# Power_Supply.net
KiCad netlist of a schematic drawn in Altium Designer
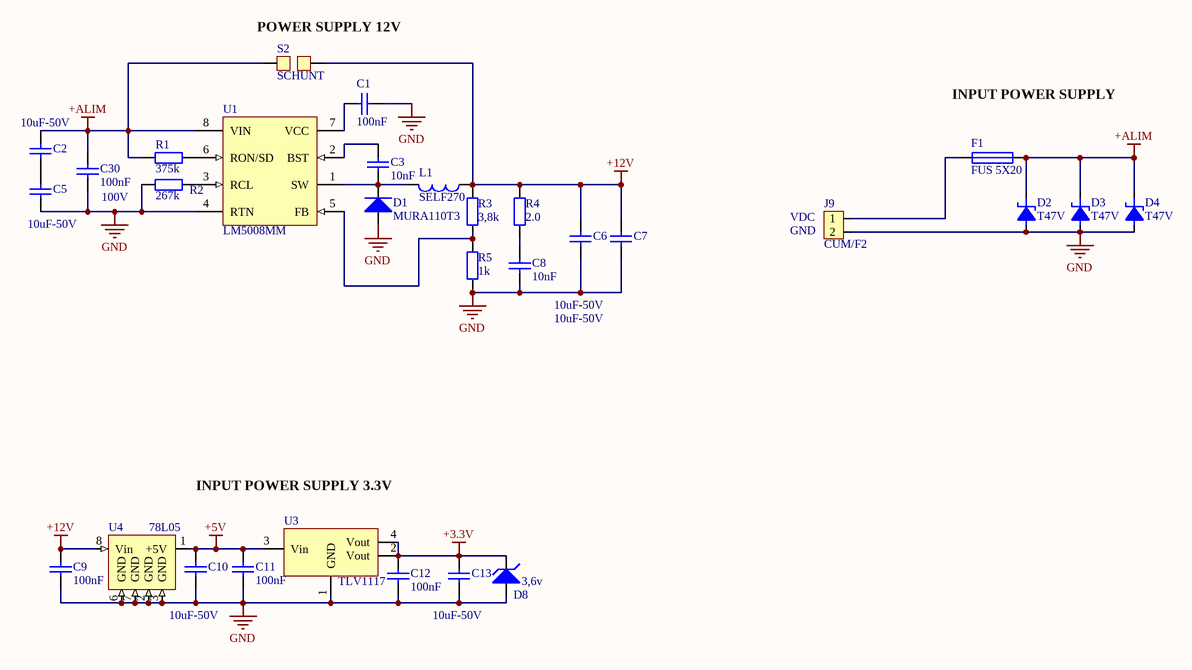
[diagram p0: Power_Supply.SchDoc]

(export (version "E")
  (design (tool "Eeschema 10.0.6"))
  (components
    (comp (ref "C1")
      (value "100nF")
      (footprint "C0603")
      (description "Capacitor")
      (libsource (lib "MyLibrary") (part "Cap"))
    )
    (comp (ref "C2")
      (value "10uF-50V")
      (footprint "C1206")
      (description "Capacitor")
      (libsource (lib "MyLibrary") (part "Cap"))
    )
    (comp (ref "C3")
      (value "10nF")
      (footprint "C0603")
      (description "Capacitor")
      (libsource (lib "MyLibrary") (part "Cap"))
    )
    (comp (ref "C5")
      (value "10uF-50V")
      (footprint "C1206")
      (description "Capacitor")
      (libsource (lib "MyLibrary") (part "Cap"))
    )
    (comp (ref "C6")
      (value "10uF-50V")
      (footprint "C1206")
      (description "Capacitor")
      (libsource (lib "MyLibrary") (part "Cap"))
    )
    (comp (ref "C7")
      (value "10uF-50V")
      (footprint "C1206")
      (description "Capacitor")
      (libsource (lib "MyLibrary") (part "Cap"))
    )
    (comp (ref "C8")
      (value "10nF")
      (footprint "C0603")
      (description "Capacitor")
      (libsource (lib "MyLibrary") (part "Cap"))
    )
    (comp (ref "C9")
      (value "100nF")
      (footprint "C0603")
      (description "Capacitor")
      (libsource (lib "MyLibrary") (part "Cap"))
    )
    (comp (ref "C10")
      (value "10uF-50V")
      (footprint "C1206")
      (description "Capacitor")
      (libsource (lib "MyLibrary") (part "Cap"))
    )
    (comp (ref "C11")
      (value "100nF")
      (footprint "C0603")
      (description "Capacitor")
      (libsource (lib "MyLibrary") (part "Cap"))
    )
    (comp (ref "C12")
      (value "100nF")
      (footprint "C0603")
      (description "Capacitor")
      (libsource (lib "MyLibrary") (part "Cap"))
    )
    (comp (ref "C13")
      (value "10uF-50V")
      (footprint "C1206")
      (description "Capacitor")
      (libsource (lib "MyLibrary") (part "Cap"))
    )
    (comp (ref "C30")
      (value "100nF")
      (footprint "C0603")
      (description "Capacitor")
      (libsource (lib "MyLibrary") (part "Cap"))
    )
    (comp (ref "D1")
      (value "MURA110T3")
      (footprint "DO-214AC")
      (description "Diode")
      (libsource (lib "MyLibrary") (part "Diode"))
    )
    (comp (ref "D2")
      (value "T47V")
      (footprint "DIO47A")
      (description "TRANSIL CMS 47V unidirectionnelle")
      (libsource (lib "PROTEL") (part "T47V"))
    )
    (comp (ref "D3")
      (value "T47V")
      (footprint "DIO47A")
      (description "TRANSIL CMS 47V unidirectionnelle")
      (libsource (lib "PROTEL") (part "T47V"))
    )
    (comp (ref "D4")
      (value "T47V")
      (footprint "DIO47A")
      (description "TRANSIL CMS 47V unidirectionnelle")
      (libsource (lib "PROTEL") (part "T47V"))
    )
    (comp (ref "D8")
      (value "3,6v")
      (footprint "SOD123")
      (description "Zener Diode")
      (libsource (lib "MyLibrary") (part "D Zener"))
    )
    (comp (ref "F1")
      (value "FUS 5X20")
      (footprint "FUSPO-A1")
      (description "FUSIBLE VERRE 5 x 20")
      (libsource (lib "PROTEL") (part "FUS 5X20"))
    )
    (comp (ref "J9")
      (value "CUM/F2")
      (footprint "CNT2H")
      (description "connecteur  2 points")
      (libsource (lib "PROTEL") (part "CUM/F2"))
    )
    (comp (ref "L1")
      (value "SELF270")
      (footprint "SELF270")
      (description "self 270uH")
      (libsource (lib "PROTEL") (part "SELF270"))
    )
    (comp (ref "R1")
      (value "375k")
      (footprint "R0603")
      (description "Thin Metal Film Resistor")
      (libsource (lib "") (part "Res_1"))
    )
    (comp (ref "R2")
      (value "267k")
      (footprint "R0603")
      (description "Thin Metal Film Resistor")
      (libsource (lib "") (part "Res_1"))
    )
    (comp (ref "R3")
      (value "3,8k")
      (footprint "R0603")
      (description "Thin Metal Film Resistor")
      (libsource (lib "MyLibrary") (part "Res"))
    )
    (comp (ref "R4")
      (value "2.0")
      (footprint "R0603")
      (description "Thin Metal Film Resistor")
      (libsource (lib "MyLibrary") (part "Res"))
    )
    (comp (ref "R5")
      (value "1k")
      (footprint "R0603")
      (description "Thin Metal Film Resistor")
      (libsource (lib "MyLibrary") (part "Res"))
    )
    (comp (ref "S2")
      (value "SCHUNT")
      (footprint "SCHUNT")
      (description "schunt 2 points")
      (libsource (lib "PROTEL") (part "SCHUNT"))
    )
    (comp (ref "U1")
      (value "LM5008MM")
      (footprint "MUA08A_M")
      (description "High Voltage (100V) Step Down Switching Regulator, 8-pin MSOP")
      (fields (field (name "MANUFACTURER") "National Semiconductor"))
      (libsource (lib "MyLibrary") (part "LM5008MM"))
    )
    (comp (ref "U3")
      (value "TLV1117")
      (footprint "SOT223")
      (description "LDO regulator 3.3V")
      (libsource (lib "MyLibrary") (part "TLV1117"))
    )
    (comp (ref "U4")
      (value "78L05")
      (footprint "REG5VE")
      (description "E:cms ;C1:faible conso; VD:TO220 debout;")
      (libsource (lib "PROTEL") (part "78L05"))
    )
  )
  (nets
    (net (code "1") (name "+3.3V") (class "Default")
      (node (ref "C12") (pin "1") (pinfunction "1_1") (pintype "passive"))
      (node (ref "C13") (pin "2") (pinfunction "2_2") (pintype "passive"))
      (node (ref "D8") (pin "2") (pinfunction "K_2") (pintype "passive"))
      (node (ref "U3") (pin "2") (pinfunction "Vout_2") (pintype "passive"))
      (node (ref "U3") (pin "4") (pinfunction "Vout_4") (pintype "passive"))
    )
    (net (code "2") (name "+5V") (class "Default")
      (node (ref "C10") (pin "2") (pinfunction "2_2") (pintype "passive"))
      (node (ref "C11") (pin "1") (pinfunction "1_1") (pintype "passive"))
      (node (ref "U3") (pin "3") (pinfunction "Vin_3") (pintype "passive"))
      (node (ref "U4") (pin "1") (pinfunction "+5V_1") (pintype "power_in"))
    )
    (net (code "3") (name "+12V") (class "Default")
      (node (ref "C6") (pin "2") (pinfunction "2_2") (pintype "passive"))
      (node (ref "C7") (pin "2") (pinfunction "2_2") (pintype "passive"))
      (node (ref "C9") (pin "1") (pinfunction "1_1") (pintype "passive"))
      (node (ref "L1") (pin "2") (pinfunction "2_2") (pintype "passive"))
      (node (ref "R3") (pin "1") (pinfunction "1_1") (pintype "passive"))
      (node (ref "R4") (pin "1") (pinfunction "1_1") (pintype "passive"))
      (node (ref "S2") (pin "1") (pinfunction "1_1") (pintype "passive"))
      (node (ref "U4") (pin "8") (pinfunction "Vin_8") (pintype "input"))
    )
    (net (code "4") (name "+ALIM") (class "Default")
      (node (ref "C2") (pin "2") (pinfunction "2_2") (pintype "passive"))
      (node (ref "C30") (pin "1") (pinfunction "1_1") (pintype "passive"))
      (node (ref "D2") (pin "1") (pintype "passive"))
      (node (ref "D3") (pin "1") (pintype "passive"))
      (node (ref "D4") (pin "1") (pintype "passive"))
      (node (ref "F1") (pin "2") (pintype "passive"))
      (node (ref "R1") (pin "2") (pinfunction "2_2") (pintype "passive"))
      (node (ref "S2") (pin "2") (pinfunction "2_2") (pintype "passive"))
      (node (ref "U1") (pin "8") (pinfunction "VIN_8") (pintype "power_in"))
    )
    (net (code "5") (name "GND") (class "Default")
      (node (ref "C1") (pin "1") (pinfunction "1_1") (pintype "passive"))
      (node (ref "C10") (pin "1") (pinfunction "1_1") (pintype "passive"))
      (node (ref "C11") (pin "2") (pinfunction "2_2") (pintype "passive"))
      (node (ref "C12") (pin "2") (pinfunction "2_2") (pintype "passive"))
      (node (ref "C13") (pin "1") (pinfunction "1_1") (pintype "passive"))
      (node (ref "C30") (pin "2") (pinfunction "2_2") (pintype "passive"))
      (node (ref "C5") (pin "1") (pinfunction "1_1") (pintype "passive"))
      (node (ref "C6") (pin "1") (pinfunction "1_1") (pintype "passive"))
      (node (ref "C7") (pin "1") (pinfunction "1_1") (pintype "passive"))
      (node (ref "C8") (pin "1") (pinfunction "1_1") (pintype "passive"))
      (node (ref "C9") (pin "2") (pinfunction "2_2") (pintype "passive"))
      (node (ref "D1") (pin "1") (pinfunction "A_1") (pintype "passive"))
      (node (ref "D2") (pin "2") (pintype "passive"))
      (node (ref "D3") (pin "2") (pintype "passive"))
      (node (ref "D4") (pin "2") (pintype "passive"))
      (node (ref "D8") (pin "1") (pinfunction "A_1") (pintype "passive"))
      (node (ref "J9") (pin "2") (pinfunction "2_2") (pintype "passive"))
      (node (ref "R2") (pin "2") (pinfunction "2_2") (pintype "passive"))
      (node (ref "R5") (pin "2") (pinfunction "2_2") (pintype "passive"))
      (node (ref "U1") (pin "4") (pinfunction "RTN_4") (pintype "power_in"))
      (node (ref "U3") (pin "1") (pinfunction "GND_1") (pintype "power_in"))
      (node (ref "U4") (pin "2") (pinfunction "GND_2") (pintype "input"))
      (node (ref "U4") (pin "3") (pinfunction "GND_3") (pintype "input"))
      (node (ref "U4") (pin "6") (pinfunction "GND_6") (pintype "input"))
      (node (ref "U4") (pin "7") (pinfunction "GND_7") (pintype "input"))
    )
    (net (code "6") (name "Net-(C2-Pad1)") (class "Default")
      (node (ref "C2") (pin "1") (pinfunction "1_1") (pintype "passive"))
      (node (ref "C5") (pin "2") (pinfunction "2_2") (pintype "passive"))
    )
    (net (code "7") (name "Net-(C8-Pad2)") (class "Default")
      (node (ref "C8") (pin "2") (pinfunction "2_2") (pintype "passive"))
      (node (ref "R4") (pin "2") (pinfunction "2_2") (pintype "passive"))
    )
    (net (code "8") (name "Net-(D1-K)") (class "Default")
      (node (ref "C3") (pin "1") (pinfunction "1_1") (pintype "passive"))
      (node (ref "D1") (pin "2") (pinfunction "K_2") (pintype "passive"))
      (node (ref "L1") (pin "1") (pinfunction "1_1") (pintype "passive"))
      (node (ref "U1") (pin "1") (pinfunction "SW_1") (pintype "power_in"))
    )
    (net (code "9") (name "Net-(F1-Pad1)") (class "Default")
      (node (ref "F1") (pin "1") (pintype "passive"))
      (node (ref "J9") (pin "1") (pinfunction "1_1") (pintype "passive"))
    )
    (net (code "10") (name "Net-(U1-BST)") (class "Default")
      (node (ref "C3") (pin "2") (pinfunction "2_2") (pintype "passive"))
      (node (ref "U1") (pin "2") (pinfunction "BST_2") (pintype "input"))
    )
    (net (code "11") (name "Net-(U1-FB)") (class "Default")
      (node (ref "R3") (pin "2") (pinfunction "2_2") (pintype "passive"))
      (node (ref "R5") (pin "1") (pinfunction "1_1") (pintype "passive"))
      (node (ref "U1") (pin "5") (pinfunction "FB_5") (pintype "input"))
    )
    (net (code "12") (name "Net-(U1-RCL)") (class "Default")
      (node (ref "R2") (pin "1") (pinfunction "1_1") (pintype "passive"))
      (node (ref "U1") (pin "3") (pinfunction "RCL_3") (pintype "input"))
    )
    (net (code "13") (name "Net-(U1-RON{slash}SD)") (class "Default")
      (node (ref "R1") (pin "1") (pinfunction "1_1") (pintype "passive"))
      (node (ref "U1") (pin "6") (pinfunction "RON/SD_6") (pintype "input"))
    )
    (net (code "14") (name "Net-(U1-VCC)") (class "Default")
      (node (ref "C1") (pin "2") (pinfunction "2_2") (pintype "passive"))
      (node (ref "U1") (pin "7") (pinfunction "VCC_7") (pintype "power_in"))
    )
  )
)
